# scale_AD7190.net
KiCad netlist of a schematic drawn in Altium Designer
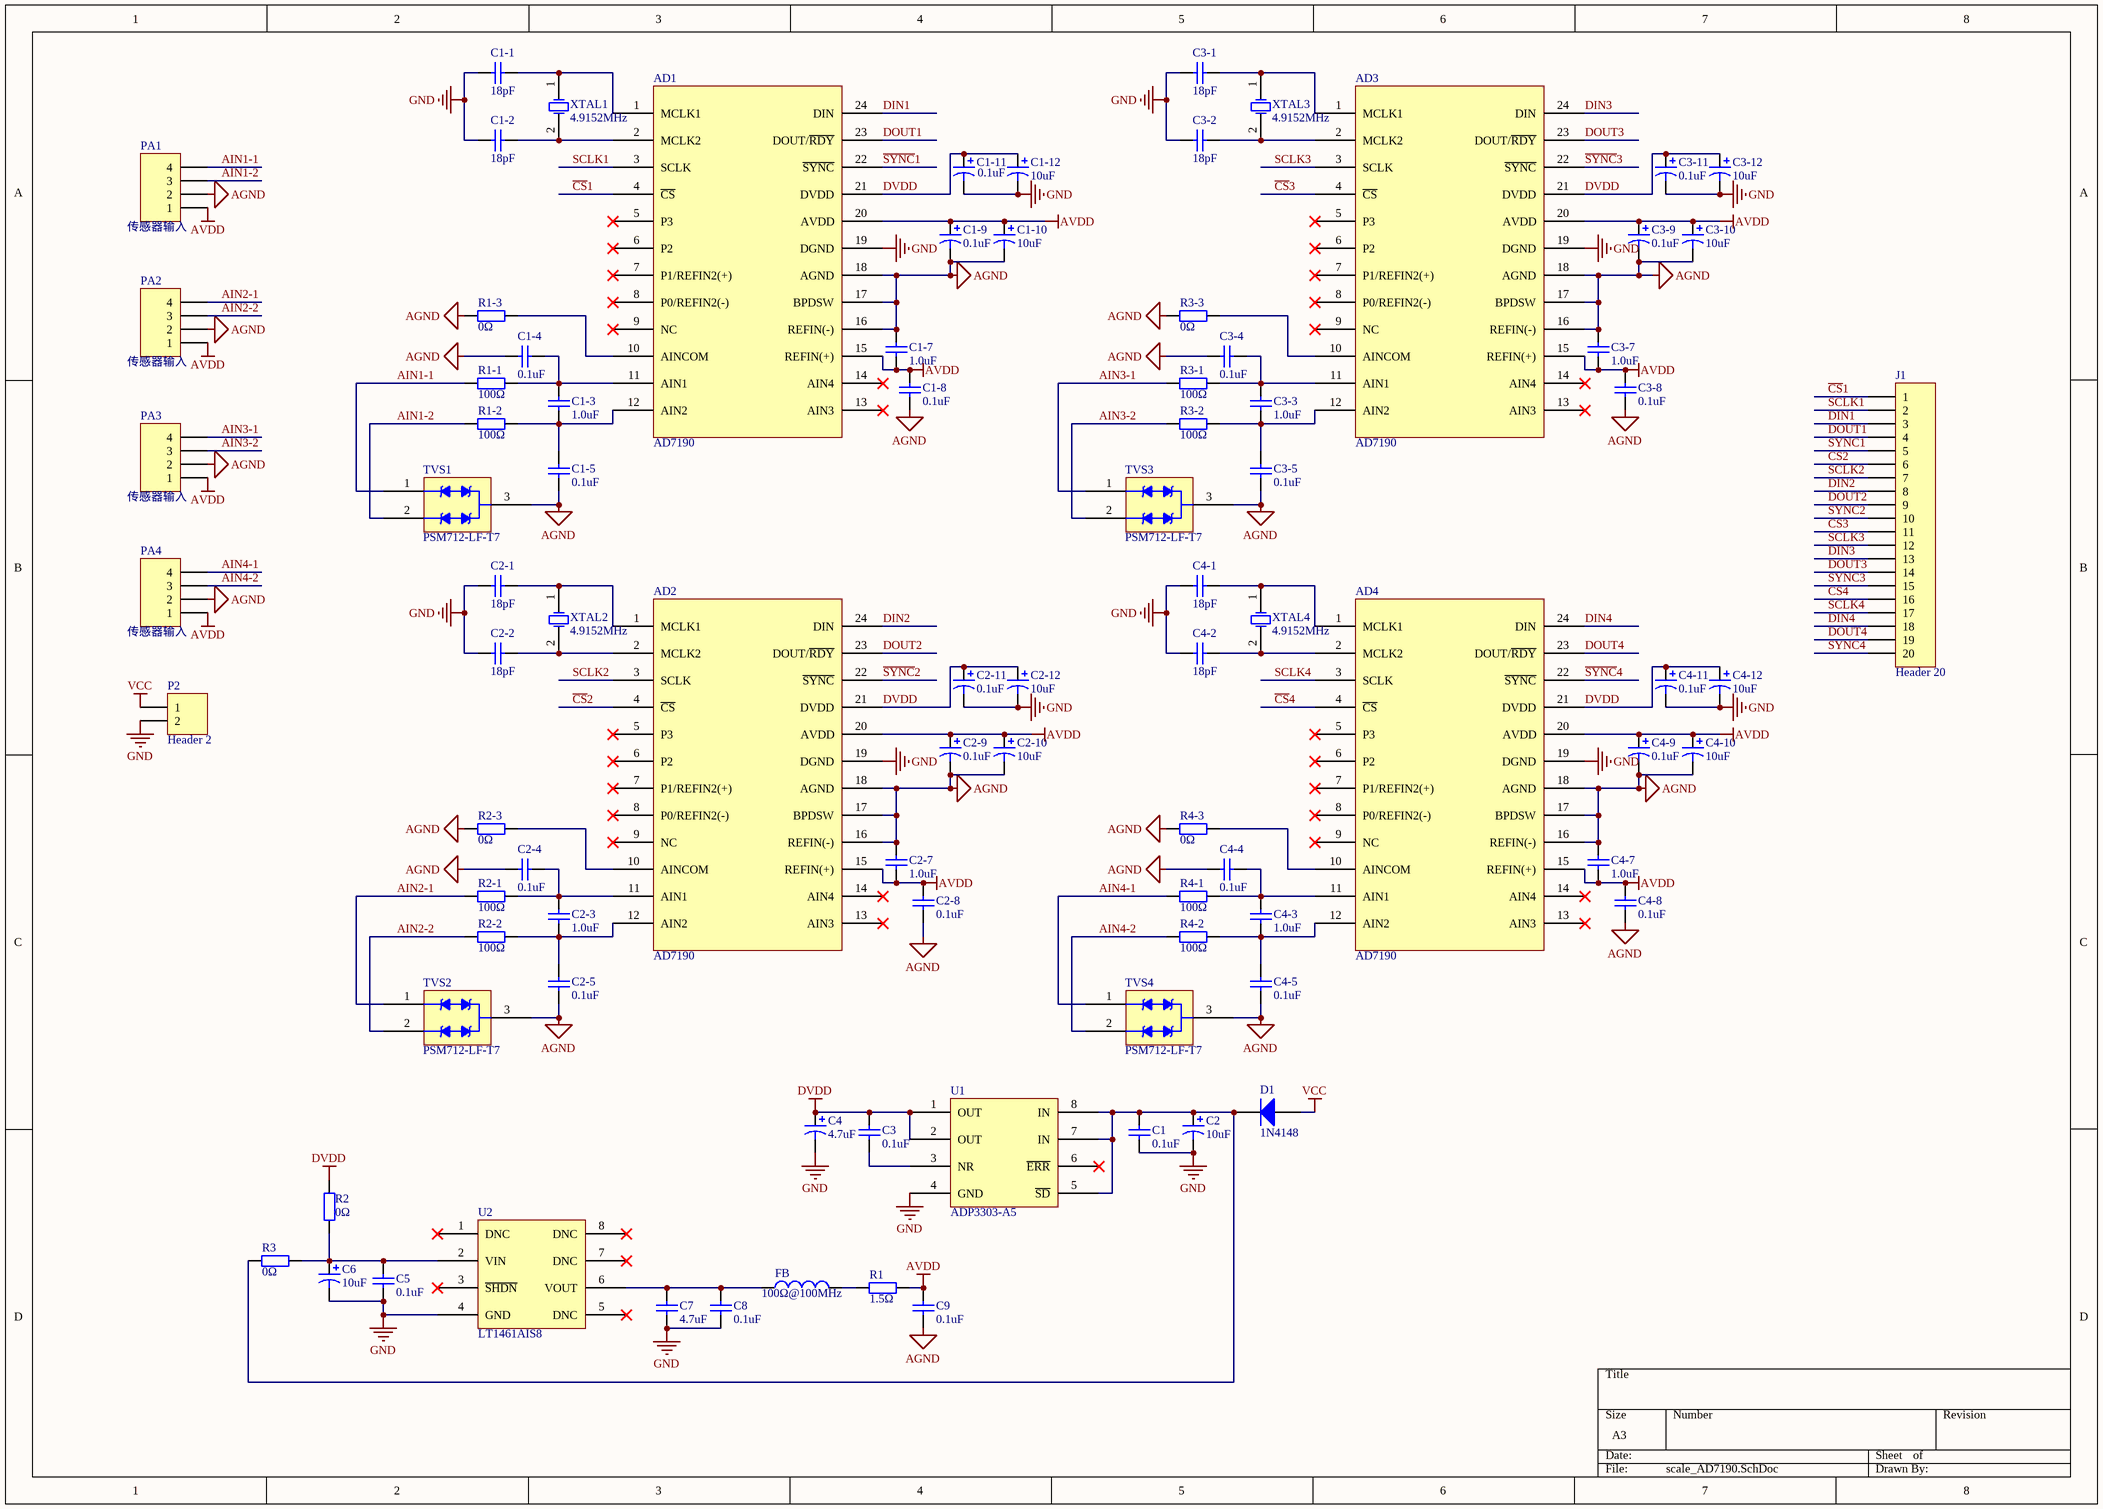
[diagram p0: scale_AD7190.SchDoc]

(export (version "E")
  (design (tool "Eeschema 10.0.6"))
  (components
    (comp (ref "AD1")
      (value "AD7190")
      (footprint "TSOP-24N_AD7190")
      (libsource (lib "scale_AD7190") (part "AD7190"))
    )
    (comp (ref "AD2")
      (value "AD7190")
      (footprint "TSOP-24N_AD7190")
      (libsource (lib "scale_AD7190") (part "AD7190"))
    )
    (comp (ref "AD3")
      (value "AD7190")
      (footprint "TSOP-24N_AD7190")
      (libsource (lib "scale_AD7190") (part "AD7190"))
    )
    (comp (ref "AD4")
      (value "AD7190")
      (footprint "TSOP-24N_AD7190")
      (libsource (lib "scale_AD7190") (part "AD7190"))
    )
    (comp (ref "C1")
      (value "0.1uF")
      (footprint "0805_C")
      (description "贴片电容")
      (libsource (lib "Miscellaneous Devices LC") (part "0402 1.0uF (105) 10% 25V"))
    )
    (comp (ref "C1-1")
      (value "18pF")
      (footprint "0805_C")
      (description "贴片电容")
      (libsource (lib "Miscellaneous Devices LC") (part "0402 15pF (150) 5% 50V"))
    )
    (comp (ref "C1-2")
      (value "18pF")
      (footprint "0805_C")
      (description "贴片电容")
      (libsource (lib "Miscellaneous Devices LC") (part "0402 15pF (150) 5% 50V"))
    )
    (comp (ref "C1-3")
      (value "1.0uF")
      (footprint "0805_C")
      (description "贴片电容")
      (libsource (lib "Miscellaneous Devices LC") (part "0402 1.0uF (105) 10% 25V"))
    )
    (comp (ref "C1-4")
      (value "0.1uF")
      (footprint "0805_C")
      (description "贴片电容")
      (libsource (lib "Miscellaneous Devices LC") (part "0402 1.0uF (105) 10% 25V"))
    )
    (comp (ref "C1-5")
      (value "0.1uF")
      (footprint "0805_C")
      (description "贴片电容")
      (libsource (lib "Miscellaneous Devices LC") (part "0402 1.0uF (105) 10% 25V"))
    )
    (comp (ref "C1-7")
      (value "1.0uF")
      (footprint "0805_C")
      (description "贴片电容")
      (libsource (lib "Miscellaneous Devices LC") (part "0402 1.0uF (105) 10% 25V"))
    )
    (comp (ref "C1-8")
      (value "0.1uF")
      (footprint "0805_C")
      (description "贴片电容")
      (libsource (lib "Miscellaneous Devices LC") (part "0402 1.0uF (105) 10% 25V"))
    )
    (comp (ref "C1-9")
      (value "0.1uF")
      (footprint "0805_C")
      (description "Polarized Capacitor (Surface Mount)")
      (fields (field (name "PUBLISHER") "Altium Limited"))
      (libsource (lib "Miscellaneous Devices") (part "Cap Pol3"))
    )
    (comp (ref "C1-10")
      (value "10uF")
      (footprint "0805_C")
      (description "Polarized Capacitor (Surface Mount)")
      (fields (field (name "PUBLISHER") "Altium Limited"))
      (libsource (lib "Miscellaneous Devices") (part "Cap Pol3"))
    )
    (comp (ref "C1-11")
      (value "0.1uF")
      (footprint "0805_C")
      (description "Polarized Capacitor (Surface Mount)")
      (fields (field (name "PUBLISHER") "Altium Limited"))
      (libsource (lib "Miscellaneous Devices") (part "Cap Pol3"))
    )
    (comp (ref "C1-12")
      (value "10uF")
      (footprint "0805_C")
      (description "Polarized Capacitor (Surface Mount)")
      (fields (field (name "PUBLISHER") "Altium Limited"))
      (libsource (lib "Miscellaneous Devices") (part "Cap Pol3"))
    )
    (comp (ref "C2")
      (value "10uF")
      (footprint "0805_C")
      (description "Polarized Capacitor (Surface Mount)")
      (fields (field (name "PUBLISHER") "Altium Limited"))
      (libsource (lib "Miscellaneous Devices") (part "Cap Pol3"))
    )
    (comp (ref "C2-1")
      (value "18pF")
      (footprint "0805_C")
      (description "贴片电容")
      (libsource (lib "Miscellaneous Devices LC") (part "0402 15pF (150) 5% 50V"))
    )
    (comp (ref "C2-2")
      (value "18pF")
      (footprint "0805_C")
      (description "贴片电容")
      (libsource (lib "Miscellaneous Devices LC") (part "0402 15pF (150) 5% 50V"))
    )
    (comp (ref "C2-3")
      (value "1.0uF")
      (footprint "0805_C")
      (description "贴片电容")
      (libsource (lib "Miscellaneous Devices LC") (part "0402 1.0uF (105) 10% 25V"))
    )
    (comp (ref "C2-4")
      (value "0.1uF")
      (footprint "0805_C")
      (description "贴片电容")
      (libsource (lib "Miscellaneous Devices LC") (part "0402 1.0uF (105) 10% 25V"))
    )
    (comp (ref "C2-5")
      (value "0.1uF")
      (footprint "0805_C")
      (description "贴片电容")
      (libsource (lib "Miscellaneous Devices LC") (part "0402 1.0uF (105) 10% 25V"))
    )
    (comp (ref "C2-7")
      (value "1.0uF")
      (footprint "0805_C")
      (description "贴片电容")
      (libsource (lib "Miscellaneous Devices LC") (part "0402 1.0uF (105) 10% 25V"))
    )
    (comp (ref "C2-8")
      (value "0.1uF")
      (footprint "0805_C")
      (description "贴片电容")
      (libsource (lib "Miscellaneous Devices LC") (part "0402 1.0uF (105) 10% 25V"))
    )
    (comp (ref "C2-9")
      (value "0.1uF")
      (footprint "0805_C")
      (description "Polarized Capacitor (Surface Mount)")
      (fields (field (name "PUBLISHER") "Altium Limited"))
      (libsource (lib "Miscellaneous Devices") (part "Cap Pol3"))
    )
    (comp (ref "C2-10")
      (value "10uF")
      (footprint "0805_C")
      (description "Polarized Capacitor (Surface Mount)")
      (fields (field (name "PUBLISHER") "Altium Limited"))
      (libsource (lib "Miscellaneous Devices") (part "Cap Pol3"))
    )
    (comp (ref "C2-11")
      (value "0.1uF")
      (footprint "0805_C")
      (description "Polarized Capacitor (Surface Mount)")
      (fields (field (name "PUBLISHER") "Altium Limited"))
      (libsource (lib "Miscellaneous Devices") (part "Cap Pol3"))
    )
    (comp (ref "C2-12")
      (value "10uF")
      (footprint "0805_C")
      (description "Polarized Capacitor (Surface Mount)")
      (fields (field (name "PUBLISHER") "Altium Limited"))
      (libsource (lib "Miscellaneous Devices") (part "Cap Pol3"))
    )
    (comp (ref "C3")
      (value "0.1uF")
      (footprint "0805_C")
      (description "贴片电容")
      (libsource (lib "Miscellaneous Devices LC") (part "0402 1.0uF (105) 10% 25V"))
    )
    (comp (ref "C3-1")
      (value "18pF")
      (footprint "0805_C")
      (description "贴片电容")
      (libsource (lib "Miscellaneous Devices LC") (part "0402 15pF (150) 5% 50V"))
    )
    (comp (ref "C3-2")
      (value "18pF")
      (footprint "0805_C")
      (description "贴片电容")
      (libsource (lib "Miscellaneous Devices LC") (part "0402 15pF (150) 5% 50V"))
    )
    (comp (ref "C3-3")
      (value "1.0uF")
      (footprint "0805_C")
      (description "贴片电容")
      (libsource (lib "Miscellaneous Devices LC") (part "0402 1.0uF (105) 10% 25V"))
    )
    (comp (ref "C3-4")
      (value "0.1uF")
      (footprint "0805_C")
      (description "贴片电容")
      (libsource (lib "Miscellaneous Devices LC") (part "0402 1.0uF (105) 10% 25V"))
    )
    (comp (ref "C3-5")
      (value "0.1uF")
      (footprint "0805_C")
      (description "贴片电容")
      (libsource (lib "Miscellaneous Devices LC") (part "0402 1.0uF (105) 10% 25V"))
    )
    (comp (ref "C3-7")
      (value "1.0uF")
      (footprint "0805_C")
      (description "贴片电容")
      (libsource (lib "Miscellaneous Devices LC") (part "0402 1.0uF (105) 10% 25V"))
    )
    (comp (ref "C3-8")
      (value "0.1uF")
      (footprint "0805_C")
      (description "贴片电容")
      (libsource (lib "Miscellaneous Devices LC") (part "0402 1.0uF (105) 10% 25V"))
    )
    (comp (ref "C3-9")
      (value "0.1uF")
      (footprint "0805_C")
      (description "Polarized Capacitor (Surface Mount)")
      (fields (field (name "PUBLISHER") "Altium Limited"))
      (libsource (lib "Miscellaneous Devices") (part "Cap Pol3"))
    )
    (comp (ref "C3-10")
      (value "10uF")
      (footprint "0805_C")
      (description "Polarized Capacitor (Surface Mount)")
      (fields (field (name "PUBLISHER") "Altium Limited"))
      (libsource (lib "Miscellaneous Devices") (part "Cap Pol3"))
    )
    (comp (ref "C3-11")
      (value "0.1uF")
      (footprint "0805_C")
      (description "Polarized Capacitor (Surface Mount)")
      (fields (field (name "PUBLISHER") "Altium Limited"))
      (libsource (lib "Miscellaneous Devices") (part "Cap Pol3"))
    )
    (comp (ref "C3-12")
      (value "10uF")
      (footprint "0805_C")
      (description "Polarized Capacitor (Surface Mount)")
      (fields (field (name "PUBLISHER") "Altium Limited"))
      (libsource (lib "Miscellaneous Devices") (part "Cap Pol3"))
    )
    (comp (ref "C4")
      (value "4.7uF")
      (footprint "0805_C")
      (description "Polarized Capacitor (Surface Mount)")
      (fields (field (name "PUBLISHER") "Altium Limited"))
      (libsource (lib "Miscellaneous Devices") (part "Cap Pol3"))
    )
    (comp (ref "C4-1")
      (value "18pF")
      (footprint "0805_C")
      (description "贴片电容")
      (libsource (lib "Miscellaneous Devices LC") (part "0402 15pF (150) 5% 50V"))
    )
    (comp (ref "C4-2")
      (value "18pF")
      (footprint "0805_C")
      (description "贴片电容")
      (libsource (lib "Miscellaneous Devices LC") (part "0402 15pF (150) 5% 50V"))
    )
    (comp (ref "C4-3")
      (value "1.0uF")
      (footprint "0805_C")
      (description "贴片电容")
      (libsource (lib "Miscellaneous Devices LC") (part "0402 1.0uF (105) 10% 25V"))
    )
    (comp (ref "C4-4")
      (value "0.1uF")
      (footprint "0805_C")
      (description "贴片电容")
      (libsource (lib "Miscellaneous Devices LC") (part "0402 1.0uF (105) 10% 25V"))
    )
    (comp (ref "C4-5")
      (value "0.1uF")
      (footprint "0805_C")
      (description "贴片电容")
      (libsource (lib "Miscellaneous Devices LC") (part "0402 1.0uF (105) 10% 25V"))
    )
    (comp (ref "C4-7")
      (value "1.0uF")
      (footprint "0805_C")
      (description "贴片电容")
      (libsource (lib "Miscellaneous Devices LC") (part "0402 1.0uF (105) 10% 25V"))
    )
    (comp (ref "C4-8")
      (value "0.1uF")
      (footprint "0805_C")
      (description "贴片电容")
      (libsource (lib "Miscellaneous Devices LC") (part "0402 1.0uF (105) 10% 25V"))
    )
    (comp (ref "C4-9")
      (value "0.1uF")
      (footprint "0805_C")
      (description "Polarized Capacitor (Surface Mount)")
      (fields (field (name "PUBLISHER") "Altium Limited"))
      (libsource (lib "Miscellaneous Devices") (part "Cap Pol3"))
    )
    (comp (ref "C4-10")
      (value "10uF")
      (footprint "0805_C")
      (description "Polarized Capacitor (Surface Mount)")
      (fields (field (name "PUBLISHER") "Altium Limited"))
      (libsource (lib "Miscellaneous Devices") (part "Cap Pol3"))
    )
    (comp (ref "C4-11")
      (value "0.1uF")
      (footprint "0805_C")
      (description "Polarized Capacitor (Surface Mount)")
      (fields (field (name "PUBLISHER") "Altium Limited"))
      (libsource (lib "Miscellaneous Devices") (part "Cap Pol3"))
    )
    (comp (ref "C4-12")
      (value "10uF")
      (footprint "0805_C")
      (description "Polarized Capacitor (Surface Mount)")
      (fields (field (name "PUBLISHER") "Altium Limited"))
      (libsource (lib "Miscellaneous Devices") (part "Cap Pol3"))
    )
    (comp (ref "C5")
      (value "0.1uF")
      (footprint "0805_C")
      (description "贴片电容")
      (libsource (lib "Miscellaneous Devices LC") (part "0402 1.0uF (105) 10% 25V"))
    )
    (comp (ref "C6")
      (value "10uF")
      (footprint "0805_C")
      (description "Polarized Capacitor (Surface Mount)")
      (fields (field (name "PUBLISHER") "Altium Limited"))
      (libsource (lib "Miscellaneous Devices") (part "Cap Pol3"))
    )
    (comp (ref "C7")
      (value "4.7uF")
      (footprint "0805_C")
      (description "贴片电容")
      (libsource (lib "Miscellaneous Devices LC") (part "0402 1.0uF (105) 10% 25V"))
    )
    (comp (ref "C8")
      (value "0.1uF")
      (footprint "0805_C")
      (description "贴片电容")
      (libsource (lib "Miscellaneous Devices LC") (part "0402 1.0uF (105) 10% 25V"))
    )
    (comp (ref "C9")
      (value "0.1uF")
      (footprint "0805_C")
      (description "贴片电容")
      (libsource (lib "Miscellaneous Devices LC") (part "0402 1.0uF (105) 10% 25V"))
    )
    (comp (ref "D1")
      (value "1N4148")
      (footprint "SOD-323")
      (description "High Conductance Fast Diode")
      (fields (field (name "PUBLISHER") "Altium Limited"))
      (libsource (lib "Miscellaneous Devices") (part "Diode 1N4148"))
    )
    (comp (ref "FB")
      (value "100Ω@100MHz")
      (footprint "0805_L")
      (description "Inductor")
      (fields (field (name "PUBLISHER") "Altium Limited"))
      (libsource (lib "Miscellaneous Devices") (part "Inductor"))
    )
    (comp (ref "J1")
      (value "Header 20")
      (footprint "HDR1X20")
      (description "Header, 20-Pin")
      (fields (field (name "PUBLISHER") "Altium Limited"))
      (libsource (lib "Miscellaneous Connectors") (part "Header 20"))
    )
    (comp (ref "P2")
      (value "Header 2")
      (footprint "端子2×5.08")
      (description "Header, 2-Pin")
      (fields (field (name "PUBLISHER") "Altium Limited"))
      (libsource (lib "Miscellaneous Connectors") (part "Header 2"))
    )
    (comp (ref "PA1")
      (value "传感器输入")
      (footprint "端子4*5.08")
      (description "Header, 4-Pin")
      (fields (field (name "PUBLISHER") "Altium Limited"))
      (libsource (lib "Miscellaneous Connectors") (part "Header 4"))
    )
    (comp (ref "PA2")
      (value "传感器输入")
      (footprint "端子4*5.08")
      (description "Header, 4-Pin")
      (fields (field (name "PUBLISHER") "Altium Limited"))
      (libsource (lib "Miscellaneous Connectors") (part "Header 4"))
    )
    (comp (ref "PA3")
      (value "传感器输入")
      (footprint "端子4*5.08")
      (description "Header, 4-Pin")
      (fields (field (name "PUBLISHER") "Altium Limited"))
      (libsource (lib "Miscellaneous Connectors") (part "Header 4"))
    )
    (comp (ref "PA4")
      (value "传感器输入")
      (footprint "端子4*5.08")
      (description "Header, 4-Pin")
      (fields (field (name "PUBLISHER") "Altium Limited"))
      (libsource (lib "Miscellaneous Connectors") (part "Header 4"))
    )
    (comp (ref "R1")
      (value "1.5Ω")
      (footprint "0805_R")
      (description "贴片电阻")
      (libsource (lib "Miscellaneous Devices LC") (part "0402 1.2KΩ (1201) 1%"))
    )
    (comp (ref "R1-1")
      (value "100Ω")
      (footprint "0805_R")
      (description "贴片电阻")
      (libsource (lib "Miscellaneous Devices LC") (part "0402 100Ω (1000) 1%"))
    )
    (comp (ref "R1-2")
      (value "100Ω")
      (footprint "0805_R")
      (description "贴片电阻")
      (libsource (lib "Miscellaneous Devices LC") (part "0402 100Ω (1000) 1%"))
    )
    (comp (ref "R1-3")
      (value "0Ω")
      (footprint "0805_R")
      (description "贴片电阻")
      (libsource (lib "Miscellaneous Devices LC") (part "0402 100Ω (1000) 1%"))
    )
    (comp (ref "R2")
      (value "0Ω")
      (footprint "0805_R")
      (description "贴片电阻")
      (libsource (lib "") (part "0402 100Ω (1000) 1%_1"))
    )
    (comp (ref "R2-1")
      (value "100Ω")
      (footprint "0805_R")
      (description "贴片电阻")
      (libsource (lib "Miscellaneous Devices LC") (part "0402 100Ω (1000) 1%"))
    )
    (comp (ref "R2-2")
      (value "100Ω")
      (footprint "0805_R")
      (description "贴片电阻")
      (libsource (lib "Miscellaneous Devices LC") (part "0402 100Ω (1000) 1%"))
    )
    (comp (ref "R2-3")
      (value "0Ω")
      (footprint "0805_R")
      (description "贴片电阻")
      (libsource (lib "Miscellaneous Devices LC") (part "0402 100Ω (1000) 1%"))
    )
    (comp (ref "R3")
      (value "0Ω")
      (footprint "0805_R")
      (description "贴片电阻")
      (libsource (lib "Miscellaneous Devices LC") (part "0402 100Ω (1000) 1%"))
    )
    (comp (ref "R3-1")
      (value "100Ω")
      (footprint "0805_R")
      (description "贴片电阻")
      (libsource (lib "Miscellaneous Devices LC") (part "0402 100Ω (1000) 1%"))
    )
    (comp (ref "R3-2")
      (value "100Ω")
      (footprint "0805_R")
      (description "贴片电阻")
      (libsource (lib "Miscellaneous Devices LC") (part "0402 100Ω (1000) 1%"))
    )
    (comp (ref "R3-3")
      (value "0Ω")
      (footprint "0805_R")
      (description "贴片电阻")
      (libsource (lib "Miscellaneous Devices LC") (part "0402 100Ω (1000) 1%"))
    )
    (comp (ref "R4-1")
      (value "100Ω")
      (footprint "0805_R")
      (description "贴片电阻")
      (libsource (lib "Miscellaneous Devices LC") (part "0402 100Ω (1000) 1%"))
    )
    (comp (ref "R4-2")
      (value "100Ω")
      (footprint "0805_R")
      (description "贴片电阻")
      (libsource (lib "Miscellaneous Devices LC") (part "0402 100Ω (1000) 1%"))
    )
    (comp (ref "R4-3")
      (value "0Ω")
      (footprint "0805_R")
      (description "贴片电阻")
      (libsource (lib "Miscellaneous Devices LC") (part "0402 100Ω (1000) 1%"))
    )
    (comp (ref "TVS1")
      (value "PSM712-LF-T7")
      (footprint "SOT-23(SOT-23-3)")
      (description "TVS")
      (libsource (lib "Miscellaneous Devices LC") (part "PSM712-LF-T7_[C32677]"))
    )
    (comp (ref "TVS2")
      (value "PSM712-LF-T7")
      (footprint "SOT-23(SOT-23-3)")
      (description "TVS")
      (libsource (lib "Miscellaneous Devices LC") (part "PSM712-LF-T7_[C32677]"))
    )
    (comp (ref "TVS3")
      (value "PSM712-LF-T7")
      (footprint "SOT-23(SOT-23-3)")
      (description "TVS")
      (libsource (lib "Miscellaneous Devices LC") (part "PSM712-LF-T7_[C32677]"))
    )
    (comp (ref "TVS4")
      (value "PSM712-LF-T7")
      (footprint "SOT-23(SOT-23-3)")
      (description "TVS")
      (libsource (lib "Miscellaneous Devices LC") (part "PSM712-LF-T7_[C32677]"))
    )
    (comp (ref "U1")
      (value "ADP3303-A5")
      (footprint "SOIC-8N-ADP3303-A5")
      (libsource (lib "scale_AD7190") (part "ADP3303"))
    )
    (comp (ref "U2")
      (value "LT1461AIS8")
      (footprint "SOIC-8N-LT1416")
      (libsource (lib "scale_AD7190") (part "LT1461AIS8"))
    )
    (comp (ref "XTAL1")
      (value "4.9152MHz")
      (footprint "SMD-3225_4P")
      (description "Crystal Oscillator")
      (fields (field (name "PUBLISHER") "Altium Limited"))
      (libsource (lib "Miscellaneous Devices") (part "XTAL"))
    )
    (comp (ref "XTAL2")
      (value "4.9152MHz")
      (footprint "SMD-3225_4P")
      (description "Crystal Oscillator")
      (fields (field (name "PUBLISHER") "Altium Limited"))
      (libsource (lib "Miscellaneous Devices") (part "XTAL"))
    )
    (comp (ref "XTAL3")
      (value "4.9152MHz")
      (footprint "SMD-3225_4P")
      (description "Crystal Oscillator")
      (fields (field (name "PUBLISHER") "Altium Limited"))
      (libsource (lib "Miscellaneous Devices") (part "XTAL"))
    )
    (comp (ref "XTAL4")
      (value "4.9152MHz")
      (footprint "SMD-3225_4P")
      (description "Crystal Oscillator")
      (fields (field (name "PUBLISHER") "Altium Limited"))
      (libsource (lib "Miscellaneous Devices") (part "XTAL"))
    )
  )
  (nets
    (net (code "1") (name "/AIN1-1") (class "Default")
      (node (ref "PA1") (pin "4") (pinfunction "4_4") (pintype "passive"))
      (node (ref "R1-1") (pin "1") (pinfunction "1_1") (pintype "passive"))
      (node (ref "TVS1") (pin "1") (pinfunction "1_1") (pintype "passive"))
    )
    (net (code "2") (name "/AIN1-2") (class "Default")
      (node (ref "PA1") (pin "3") (pinfunction "3_3") (pintype "passive"))
      (node (ref "R1-2") (pin "1") (pinfunction "1_1") (pintype "passive"))
      (node (ref "TVS1") (pin "2") (pinfunction "2_2") (pintype "passive"))
    )
    (net (code "3") (name "/AIN2-1") (class "Default")
      (node (ref "PA2") (pin "4") (pinfunction "4_4") (pintype "passive"))
      (node (ref "R2-1") (pin "1") (pinfunction "1_1") (pintype "passive"))
      (node (ref "TVS2") (pin "1") (pinfunction "1_1") (pintype "passive"))
    )
    (net (code "4") (name "/AIN2-2") (class "Default")
      (node (ref "PA2") (pin "3") (pinfunction "3_3") (pintype "passive"))
      (node (ref "R2-2") (pin "1") (pinfunction "1_1") (pintype "passive"))
      (node (ref "TVS2") (pin "2") (pinfunction "2_2") (pintype "passive"))
    )
    (net (code "5") (name "/AIN3-1") (class "Default")
      (node (ref "PA3") (pin "4") (pinfunction "4_4") (pintype "passive"))
      (node (ref "R3-1") (pin "1") (pinfunction "1_1") (pintype "passive"))
      (node (ref "TVS3") (pin "1") (pinfunction "1_1") (pintype "passive"))
    )
    (net (code "6") (name "/AIN3-2") (class "Default")
      (node (ref "PA3") (pin "3") (pinfunction "3_3") (pintype "passive"))
      (node (ref "R3-2") (pin "1") (pinfunction "1_1") (pintype "passive"))
      (node (ref "TVS3") (pin "2") (pinfunction "2_2") (pintype "passive"))
    )
    (net (code "7") (name "/AIN4-1") (class "Default")
      (node (ref "PA4") (pin "4") (pinfunction "4_4") (pintype "passive"))
      (node (ref "R4-1") (pin "1") (pinfunction "1_1") (pintype "passive"))
      (node (ref "TVS4") (pin "1") (pinfunction "1_1") (pintype "passive"))
    )
    (net (code "8") (name "/AIN4-2") (class "Default")
      (node (ref "PA4") (pin "3") (pinfunction "3_3") (pintype "passive"))
      (node (ref "R4-2") (pin "1") (pinfunction "1_1") (pintype "passive"))
      (node (ref "TVS4") (pin "2") (pinfunction "2_2") (pintype "passive"))
    )
    (net (code "9") (name "/DIN1") (class "Default")
      (node (ref "AD1") (pin "24") (pinfunction "DIN_24") (pintype "passive"))
      (node (ref "J1") (pin "3") (pinfunction "3_3") (pintype "passive"))
    )
    (net (code "10") (name "/DIN2") (class "Default")
      (node (ref "AD2") (pin "24") (pinfunction "DIN_24") (pintype "passive"))
      (node (ref "J1") (pin "8") (pinfunction "8_8") (pintype "passive"))
    )
    (net (code "11") (name "/DIN3") (class "Default")
      (node (ref "AD3") (pin "24") (pinfunction "DIN_24") (pintype "passive"))
      (node (ref "J1") (pin "13") (pinfunction "13_13") (pintype "passive"))
    )
    (net (code "12") (name "/DIN4") (class "Default")
      (node (ref "AD4") (pin "24") (pinfunction "DIN_24") (pintype "passive"))
      (node (ref "J1") (pin "18") (pinfunction "18_18") (pintype "passive"))
    )
    (net (code "13") (name "/DOUT1") (class "Default")
      (node (ref "AD1") (pin "23") (pinfunction "DOUT/~{RDY}_23") (pintype "passive"))
      (node (ref "J1") (pin "4") (pinfunction "4_4") (pintype "passive"))
    )
    (net (code "14") (name "/DOUT2") (class "Default")
      (node (ref "AD2") (pin "23") (pinfunction "DOUT/~{RDY}_23") (pintype "passive"))
      (node (ref "J1") (pin "9") (pinfunction "9_9") (pintype "passive"))
    )
    (net (code "15") (name "/DOUT3") (class "Default")
      (node (ref "AD3") (pin "23") (pinfunction "DOUT/~{RDY}_23") (pintype "passive"))
      (node (ref "J1") (pin "14") (pinfunction "14_14") (pintype "passive"))
    )
    (net (code "16") (name "/DOUT4") (class "Default")
      (node (ref "AD4") (pin "23") (pinfunction "DOUT/~{RDY}_23") (pintype "passive"))
      (node (ref "J1") (pin "19") (pinfunction "19_19") (pintype "passive"))
    )
    (net (code "17") (name "/SCLK1") (class "Default")
      (node (ref "AD1") (pin "3") (pinfunction "SCLK_3") (pintype "passive"))
      (node (ref "J1") (pin "2") (pinfunction "2_2") (pintype "passive"))
    )
    (net (code "18") (name "/SCLK2") (class "Default")
      (node (ref "AD2") (pin "3") (pinfunction "SCLK_3") (pintype "passive"))
      (node (ref "J1") (pin "7") (pinfunction "7_7") (pintype "passive"))
    )
    (net (code "19") (name "/SCLK3") (class "Default")
      (node (ref "AD3") (pin "3") (pinfunction "SCLK_3") (pintype "passive"))
      (node (ref "J1") (pin "12") (pinfunction "12_12") (pintype "passive"))
    )
    (net (code "20") (name "/SCLK4") (class "Default")
      (node (ref "AD4") (pin "3") (pinfunction "SCLK_3") (pintype "passive"))
      (node (ref "J1") (pin "17") (pinfunction "17_17") (pintype "passive"))
    )
    (net (code "21") (name "/~{CS}1") (class "Default")
      (node (ref "AD1") (pin "4") (pinfunction "~{CS}_4") (pintype "passive"))
      (node (ref "J1") (pin "1") (pinfunction "1_1") (pintype "passive"))
    )
    (net (code "22") (name "/~{CS}2") (class "Default")
      (node (ref "AD2") (pin "4") (pinfunction "~{CS}_4") (pintype "passive"))
      (node (ref "J1") (pin "6") (pinfunction "6_6") (pintype "passive"))
    )
    (net (code "23") (name "/~{CS}3") (class "Default")
      (node (ref "AD3") (pin "4") (pinfunction "~{CS}_4") (pintype "passive"))
      (node (ref "J1") (pin "11") (pinfunction "11_11") (pintype "passive"))
    )
    (net (code "24") (name "/~{CS}4") (class "Default")
      (node (ref "AD4") (pin "4") (pinfunction "~{CS}_4") (pintype "passive"))
      (node (ref "J1") (pin "16") (pinfunction "16_16") (pintype "passive"))
    )
    (net (code "25") (name "/~{SYNC}1") (class "Default")
      (node (ref "AD1") (pin "22") (pinfunction "~{SYNC}_22") (pintype "passive"))
      (node (ref "J1") (pin "5") (pinfunction "5_5") (pintype "passive"))
    )
    (net (code "26") (name "/~{SYNC}2") (class "Default")
      (node (ref "AD2") (pin "22") (pinfunction "~{SYNC}_22") (pintype "passive"))
      (node (ref "J1") (pin "10") (pinfunction "10_10") (pintype "passive"))
    )
    (net (code "27") (name "/~{SYNC}3") (class "Default")
      (node (ref "AD3") (pin "22") (pinfunction "~{SYNC}_22") (pintype "passive"))
      (node (ref "J1") (pin "15") (pinfunction "15_15") (pintype "passive"))
    )
    (net (code "28") (name "/~{SYNC}4") (class "Default")
      (node (ref "AD4") (pin "22") (pinfunction "~{SYNC}_22") (pintype "passive"))
      (node (ref "J1") (pin "20") (pinfunction "20_20") (pintype "passive"))
    )
    (net (code "29") (name "AGND") (class "Default")
      (node (ref "AD1") (pin "16") (pinfunction "REFIN(-)_16") (pintype "passive"))
      (node (ref "AD1") (pin "17") (pinfunction "BPDSW_17") (pintype "passive"))
      (node (ref "AD1") (pin "18") (pinfunction "AGND_18") (pintype "passive"))
      (node (ref "AD2") (pin "16") (pinfunction "REFIN(-)_16") (pintype "passive"))
      (node (ref "AD2") (pin "17") (pinfunction "BPDSW_17") (pintype "passive"))
      (node (ref "AD2") (pin "18") (pinfunction "AGND_18") (pintype "passive"))
      (node (ref "AD3") (pin "16") (pinfunction "REFIN(-)_16") (pintype "passive"))
      (node (ref "AD3") (pin "17") (pinfunction "BPDSW_17") (pintype "passive"))
      (node (ref "AD3") (pin "18") (pinfunction "AGND_18") (pintype "passive"))
      (node (ref "AD4") (pin "16") (pinfunction "REFIN(-)_16") (pintype "passive"))
      (node (ref "AD4") (pin "17") (pinfunction "BPDSW_17") (pintype "passive"))
      (node (ref "AD4") (pin "18") (pinfunction "AGND_18") (pintype "passive"))
      (node (ref "C1-10") (pin "2") (pinfunction "2_2") (pintype "passive"))
      (node (ref "C1-4") (pin "2") (pinfunction "2_2") (pintype "passive"))
      (node (ref "C1-5") (pin "2") (pinfunction "2_2") (pintype "passive"))
      (node (ref "C1-7") (pin "1") (pinfunction "1_1") (pintype "passive"))
      (node (ref "C1-8") (pin "1") (pinfunction "1_1") (pintype "passive"))
      (node (ref "C1-9") (pin "2") (pinfunction "2_2") (pintype "passive"))
      (node (ref "C2-10") (pin "2") (pinfunction "2_2") (pintype "passive"))
      (node (ref "C2-4") (pin "2") (pinfunction "2_2") (pintype "passive"))
      (node (ref "C2-5") (pin "2") (pinfunction "2_2") (pintype "passive"))
      (node (ref "C2-7") (pin "1") (pinfunction "1_1") (pintype "passive"))
      (node (ref "C2-8") (pin "1") (pinfunction "1_1") (pintype "passive"))
      (node (ref "C2-9") (pin "2") (pinfunction "2_2") (pintype "passive"))
      (node (ref "C3-10") (pin "2") (pinfunction "2_2") (pintype "passive"))
      (node (ref "C3-4") (pin "2") (pinfunction "2_2") (pintype "passive"))
      (node (ref "C3-5") (pin "2") (pinfunction "2_2") (pintype "passive"))
      (node (ref "C3-7") (pin "1") (pinfunction "1_1") (pintype "passive"))
      (node (ref "C3-8") (pin "1") (pinfunction "1_1") (pintype "passive"))
      (node (ref "C3-9") (pin "2") (pinfunction "2_2") (pintype "passive"))
      (node (ref "C4-10") (pin "2") (pinfunction "2_2") (pintype "passive"))
      (node (ref "C4-4") (pin "2") (pinfunction "2_2") (pintype "passive"))
      (node (ref "C4-5") (pin "2") (pinfunction "2_2") (pintype "passive"))
      (node (ref "C4-7") (pin "1") (pinfunction "1_1") (pintype "passive"))
      (node (ref "C4-8") (pin "1") (pinfunction "1_1") (pintype "passive"))
      (node (ref "C4-9") (pin "2") (pinfunction "2_2") (pintype "passive"))
      (node (ref "C9") (pin "2") (pinfunction "2_2") (pintype "passive"))
      (node (ref "PA1") (pin "2") (pinfunction "2_2") (pintype "passive"))
      (node (ref "PA2") (pin "2") (pinfunction "2_2") (pintype "passive"))
      (node (ref "PA3") (pin "2") (pinfunction "2_2") (pintype "passive"))
      (node (ref "PA4") (pin "2") (pinfunction "2_2") (pintype "passive"))
      (node (ref "R1-3") (pin "1") (pinfunction "1_1") (pintype "passive"))
      (node (ref "R2-3") (pin "1") (pinfunction "1_1") (pintype "passive"))
      (node (ref "R3-3") (pin "1") (pinfunction "1_1") (pintype "passive"))
      (node (ref "R4-3") (pin "1") (pinfunction "1_1") (pintype "passive"))
      (node (ref "TVS1") (pin "3") (pinfunction "3_3") (pintype "passive"))
      (node (ref "TVS2") (pin "3") (pinfunction "3_3") (pintype "passive"))
      (node (ref "TVS3") (pin "3") (pinfunction "3_3") (pintype "passive"))
      (node (ref "TVS4") (pin "3") (pinfunction "3_3") (pintype "passive"))
    )
    (net (code "30") (name "AVDD") (class "Default")
      (node (ref "AD1") (pin "15") (pinfunction "REFIN(+)_15") (pintype "passive"))
      (node (ref "AD1") (pin "20") (pinfunction "AVDD_20") (pintype "passive"))
      (node (ref "AD2") (pin "15") (pinfunction "REFIN(+)_15") (pintype "passive"))
      (node (ref "AD2") (pin "20") (pinfunction "AVDD_20") (pintype "passive"))
      (node (ref "AD3") (pin "15") (pinfunction "REFIN(+)_15") (pintype "passive"))
      (node (ref "AD3") (pin "20") (pinfunction "AVDD_20") (pintype "passive"))
      (node (ref "AD4") (pin "15") (pinfunction "REFIN(+)_15") (pintype "passive"))
      (node (ref "AD4") (pin "20") (pinfunction "AVDD_20") (pintype "passive"))
      (node (ref "C1-10") (pin "1") (pinfunction "1_1") (pintype "passive"))
      (node (ref "C1-7") (pin "2") (pinfunction "2_2") (pintype "passive"))
      (node (ref "C1-8") (pin "2") (pinfunction "2_2") (pintype "passive"))
      (node (ref "C1-9") (pin "1") (pinfunction "1_1") (pintype "passive"))
      (node (ref "C2-10") (pin "1") (pinfunction "1_1") (pintype "passive"))
      (node (ref "C2-7") (pin "2") (pinfunction "2_2") (pintype "passive"))
      (node (ref "C2-8") (pin "2") (pinfunction "2_2") (pintype "passive"))
      (node (ref "C2-9") (pin "1") (pinfunction "1_1") (pintype "passive"))
      (node (ref "C3-10") (pin "1") (pinfunction "1_1") (pintype "passive"))
      (node (ref "C3-7") (pin "2") (pinfunction "2_2") (pintype "passive"))
      (node (ref "C3-8") (pin "2") (pinfunction "2_2") (pintype "passive"))
      (node (ref "C3-9") (pin "1") (pinfunction "1_1") (pintype "passive"))
      (node (ref "C4-10") (pin "1") (pinfunction "1_1") (pintype "passive"))
      (node (ref "C4-7") (pin "2") (pinfunction "2_2") (pintype "passive"))
      (node (ref "C4-8") (pin "2") (pinfunction "2_2") (pintype "passive"))
      (node (ref "C4-9") (pin "1") (pinfunction "1_1") (pintype "passive"))
      (node (ref "C9") (pin "1") (pinfunction "1_1") (pintype "passive"))
      (node (ref "PA1") (pin "1") (pinfunction "1_1") (pintype "passive"))
      (node (ref "PA2") (pin "1") (pinfunction "1_1") (pintype "passive"))
      (node (ref "PA3") (pin "1") (pinfunction "1_1") (pintype "passive"))
      (node (ref "PA4") (pin "1") (pinfunction "1_1") (pintype "passive"))
      (node (ref "R1") (pin "2") (pinfunction "2_2") (pintype "passive"))
    )
    (net (code "31") (name "DVDD") (class "Default")
      (node (ref "AD1") (pin "21") (pinfunction "DVDD_21") (pintype "passive"))
      (node (ref "AD2") (pin "21") (pinfunction "DVDD_21") (pintype "passive"))
      (node (ref "AD3") (pin "21") (pinfunction "DVDD_21") (pintype "passive"))
      (node (ref "AD4") (pin "21") (pinfunction "DVDD_21") (pintype "passive"))
      (node (ref "C1-11") (pin "1") (pinfunction "1_1") (pintype "passive"))
      (node (ref "C1-12") (pin "1") (pinfunction "1_1") (pintype "passive"))
      (node (ref "C2-11") (pin "1") (pinfunction "1_1") (pintype "passive"))
      (node (ref "C2-12") (pin "1") (pinfunction "1_1") (pintype "passive"))
      (node (ref "C3") (pin "1") (pinfunction "1_1") (pintype "passive"))
      (node (ref "C3-11") (pin "1") (pinfunction "1_1") (pintype "passive"))
      (node (ref "C3-12") (pin "1") (pinfunction "1_1") (pintype "passive"))
      (node (ref "C4") (pin "1") (pinfunction "1_1") (pintype "passive"))
      (node (ref "C4-11") (pin "1") (pinfunction "1_1") (pintype "passive"))
      (node (ref "C4-12") (pin "1") (pinfunction "1_1") (pintype "passive"))
      (node (ref "R2") (pin "2") (pinfunction "2_2") (pintype "passive"))
      (node (ref "U1") (pin "1") (pinfunction "OUT_1") (pintype "passive"))
      (node (ref "U1") (pin "2") (pinfunction "OUT_2") (pintype "passive"))
    )
    (net (code "32") (name "GND") (class "Default")
      (node (ref "AD1") (pin "19") (pinfunction "DGND_19") (pintype "passive"))
      (node (ref "AD2") (pin "19") (pinfunction "DGND_19") (pintype "passive"))
      (node (ref "AD3") (pin "19") (pinfunction "DGND_19") (pintype "passive"))
      (node (ref "AD4") (pin "19") (pinfunction "DGND_19") (pintype "passive"))
      (node (ref "C1") (pin "2") (pinfunction "2_2") (pintype "passive"))
      (node (ref "C1-1") (pin "1") (pinfunction "1_1") (pintype "passive"))
      (node (ref "C1-11") (pin "2") (pinfunction "2_2") (pintype "passive"))
      (node (ref "C1-12") (pin "2") (pinfunction "2_2") (pintype "passive"))
      (node (ref "C1-2") (pin "1") (pinfunction "1_1") (pintype "passive"))
      (node (ref "C2") (pin "2") (pinfunction "2_2") (pintype "passive"))
      (node (ref "C2-1") (pin "1") (pinfunction "1_1") (pintype "passive"))
      (node (ref "C2-11") (pin "2") (pinfunction "2_2") (pintype "passive"))
      (node (ref "C2-12") (pin "2") (pinfunction "2_2") (pintype "passive"))
      (node (ref "C2-2") (pin "1") (pinfunction "1_1") (pintype "passive"))
      (node (ref "C3-1") (pin "1") (pinfunction "1_1") (pintype "passive"))
      (node (ref "C3-11") (pin "2") (pinfunction "2_2") (pintype "passive"))
      (node (ref "C3-12") (pin "2") (pinfunction "2_2") (pintype "passive"))
      (node (ref "C3-2") (pin "1") (pinfunction "1_1") (pintype "passive"))
      (node (ref "C4") (pin "2") (pinfunction "2_2") (pintype "passive"))
      (node (ref "C4-1") (pin "1") (pinfunction "1_1") (pintype "passive"))
      (node (ref "C4-11") (pin "2") (pinfunction "2_2") (pintype "passive"))
      (node (ref "C4-12") (pin "2") (pinfunction "2_2") (pintype "passive"))
      (node (ref "C4-2") (pin "1") (pinfunction "1_1") (pintype "passive"))
      (node (ref "C5") (pin "2") (pinfunction "2_2") (pintype "passive"))
      (node (ref "C6") (pin "2") (pinfunction "2_2") (pintype "passive"))
      (node (ref "C7") (pin "2") (pinfunction "2_2") (pintype "passive"))
      (node (ref "C8") (pin "2") (pinfunction "2_2") (pintype "passive"))
      (node (ref "P2") (pin "2") (pinfunction "2_2") (pintype "passive"))
      (node (ref "U1") (pin "4") (pinfunction "GND_4") (pintype "passive"))
      (node (ref "U2") (pin "4") (pinfunction "GND_4") (pintype "passive"))
    )
    (net (code "33") (name "Net-(AD1-AIN1)") (class "Default")
      (node (ref "AD1") (pin "11") (pinfunction "AIN1_11") (pintype "passive"))
      (node (ref "C1-3") (pin "2") (pinfunction "2_2") (pintype "passive"))
      (node (ref "C1-4") (pin "1") (pinfunction "1_1") (pintype "passive"))
      (node (ref "R1-1") (pin "2") (pinfunction "2_2") (pintype "passive"))
    )
    (net (code "34") (name "Net-(AD1-AIN2)") (class "Default")
      (node (ref "AD1") (pin "12") (pinfunction "AIN2_12") (pintype "passive"))
      (node (ref "C1-3") (pin "1") (pinfunction "1_1") (pintype "passive"))
      (node (ref "C1-5") (pin "1") (pinfunction "1_1") (pintype "passive"))
      (node (ref "R1-2") (pin "2") (pinfunction "2_2") (pintype "passive"))
    )
    (net (code "35") (name "Net-(AD1-AINCOM)") (class "Default")
      (node (ref "AD1") (pin "10") (pinfunction "AINCOM_10") (pintype "passive"))
      (node (ref "R1-3") (pin "2") (pinfunction "2_2") (pintype "passive"))
    )
    (net (code "36") (name "Net-(AD1-MCLK1)") (class "Default")
      (node (ref "AD1") (pin "1") (pinfunction "MCLK1_1") (pintype "passive"))
      (node (ref "C1-1") (pin "2") (pinfunction "2_2") (pintype "passive"))
      (node (ref "XTAL1") (pin "1") (pinfunction "OSC1_1") (pintype "passive"))
    )
    (net (code "37") (name "Net-(AD1-MCLK2)") (class "Default")
      (node (ref "AD1") (pin "2") (pinfunction "MCLK2_2") (pintype "passive"))
      (node (ref "C1-2") (pin "2") (pinfunction "2_2") (pintype "passive"))
      (node (ref "XTAL1") (pin "2") (pinfunction "OSC2_2") (pintype "passive"))
    )
    (net (code "38") (name "Net-(AD2-AIN1)") (class "Default")
      (node (ref "AD2") (pin "11") (pinfunction "AIN1_11") (pintype "passive"))
      (node (ref "C2-3") (pin "2") (pinfunction "2_2") (pintype "passive"))
      (node (ref "C2-4") (pin "1") (pinfunction "1_1") (pintype "passive"))
      (node (ref "R2-1") (pin "2") (pinfunction "2_2") (pintype "passive"))
    )
    (net (code "39") (name "Net-(AD2-AIN2)") (class "Default")
      (node (ref "AD2") (pin "12") (pinfunction "AIN2_12") (pintype "passive"))
      (node (ref "C2-3") (pin "1") (pinfunction "1_1") (pintype "passive"))
      (node (ref "C2-5") (pin "1") (pinfunction "1_1") (pintype "passive"))
      (node (ref "R2-2") (pin "2") (pinfunction "2_2") (pintype "passive"))
    )
    (net (code "40") (name "Net-(AD2-AINCOM)") (class "Default")
      (node (ref "AD2") (pin "10") (pinfunction "AINCOM_10") (pintype "passive"))
      (node (ref "R2-3") (pin "2") (pinfunction "2_2") (pintype "passive"))
    )
    (net (code "41") (name "Net-(AD2-MCLK1)") (class "Default")
      (node (ref "AD2") (pin "1") (pinfunction "MCLK1_1") (pintype "passive"))
      (node (ref "C2-1") (pin "2") (pinfunction "2_2") (pintype "passive"))
      (node (ref "XTAL2") (pin "1") (pinfunction "OSC1_1") (pintype "passive"))
    )
    (net (code "42") (name "Net-(AD2-MCLK2)") (class "Default")
      (node (ref "AD2") (pin "2") (pinfunction "MCLK2_2") (pintype "passive"))
      (node (ref "C2-2") (pin "2") (pinfunction "2_2") (pintype "passive"))
      (node (ref "XTAL2") (pin "2") (pinfunction "OSC2_2") (pintype "passive"))
    )
    (net (code "43") (name "Net-(AD3-AIN1)") (class "Default")
      (node (ref "AD3") (pin "11") (pinfunction "AIN1_11") (pintype "passive"))
      (node (ref "C3-3") (pin "2") (pinfunction "2_2") (pintype "passive"))
      (node (ref "C3-4") (pin "1") (pinfunction "1_1") (pintype "passive"))
      (node (ref "R3-1") (pin "2") (pinfunction "2_2") (pintype "passive"))
    )
    (net (code "44") (name "Net-(AD3-AIN2)") (class "Default")
      (node (ref "AD3") (pin "12") (pinfunction "AIN2_12") (pintype "passive"))
      (node (ref "C3-3") (pin "1") (pinfunction "1_1") (pintype "passive"))
      (node (ref "C3-5") (pin "1") (pinfunction "1_1") (pintype "passive"))
      (node (ref "R3-2") (pin "2") (pinfunction "2_2") (pintype "passive"))
    )
    (net (code "45") (name "Net-(AD3-AINCOM)") (class "Default")
      (node (ref "AD3") (pin "10") (pinfunction "AINCOM_10") (pintype "passive"))
      (node (ref "R3-3") (pin "2") (pinfunction "2_2") (pintype "passive"))
    )
    (net (code "46") (name "Net-(AD3-MCLK1)") (class "Default")
      (node (ref "AD3") (pin "1") (pinfunction "MCLK1_1") (pintype "passive"))
      (node (ref "C3-1") (pin "2") (pinfunction "2_2") (pintype "passive"))
      (node (ref "XTAL3") (pin "1") (pinfunction "OSC1_1") (pintype "passive"))
    )
    (net (code "47") (name "Net-(AD3-MCLK2)") (class "Default")
      (node (ref "AD3") (pin "2") (pinfunction "MCLK2_2") (pintype "passive"))
      (node (ref "C3-2") (pin "2") (pinfunction "2_2") (pintype "passive"))
      (node (ref "XTAL3") (pin "2") (pinfunction "OSC2_2") (pintype "passive"))
    )
    (net (code "48") (name "Net-(AD4-AIN1)") (class "Default")
      (node (ref "AD4") (pin "11") (pinfunction "AIN1_11") (pintype "passive"))
      (node (ref "C4-3") (pin "2") (pinfunction "2_2") (pintype "passive"))
      (node (ref "C4-4") (pin "1") (pinfunction "1_1") (pintype "passive"))
      (node (ref "R4-1") (pin "2") (pinfunction "2_2") (pintype "passive"))
    )
    (net (code "49") (name "Net-(AD4-AIN2)") (class "Default")
      (node (ref "AD4") (pin "12") (pinfunction "AIN2_12") (pintype "passive"))
      (node (ref "C4-3") (pin "1") (pinfunction "1_1") (pintype "passive"))
      (node (ref "C4-5") (pin "1") (pinfunction "1_1") (pintype "passive"))
      (node (ref "R4-2") (pin "2") (pinfunction "2_2") (pintype "passive"))
    )
    (net (code "50") (name "Net-(AD4-AINCOM)") (class "Default")
      (node (ref "AD4") (pin "10") (pinfunction "AINCOM_10") (pintype "passive"))
      (node (ref "R4-3") (pin "2") (pinfunction "2_2") (pintype "passive"))
    )
    (net (code "51") (name "Net-(AD4-MCLK1)") (class "Default")
      (node (ref "AD4") (pin "1") (pinfunction "MCLK1_1") (pintype "passive"))
      (node (ref "C4-1") (pin "2") (pinfunction "2_2") (pintype "passive"))
      (node (ref "XTAL4") (pin "1") (pinfunction "OSC1_1") (pintype "passive"))
    )
    (net (code "52") (name "Net-(AD4-MCLK2)") (class "Default")
      (node (ref "AD4") (pin "2") (pinfunction "MCLK2_2") (pintype "passive"))
      (node (ref "C4-2") (pin "2") (pinfunction "2_2") (pintype "passive"))
      (node (ref "XTAL4") (pin "2") (pinfunction "OSC2_2") (pintype "passive"))
    )
    (net (code "53") (name "Net-(D1-K)") (class "Default")
      (node (ref "C1") (pin "1") (pinfunction "1_1") (pintype "passive"))
      (node (ref "C2") (pin "1") (pinfunction "1_1") (pintype "passive"))
      (node (ref "D1") (pin "2") (pinfunction "K_2") (pintype "passive"))
      (node (ref "R3") (pin "1") (pinfunction "1_1") (pintype "passive"))
      (node (ref "U1") (pin "5") (pinfunction "~{SD}_5") (pintype "passive"))
      (node (ref "U1") (pin "7") (pinfunction "IN_7") (pintype "passive"))
      (node (ref "U1") (pin "8") (pinfunction "IN_8") (pintype "passive"))
    )
    (net (code "54") (name "Net-(FB-Pad2)") (class "Default")
      (node (ref "FB") (pin "2") (pinfunction "2_2") (pintype "passive"))
      (node (ref "R1") (pin "1") (pinfunction "1_1") (pintype "passive"))
    )
    (net (code "55") (name "Net-(U1-NR)") (class "Default")
      (node (ref "C3") (pin "2") (pinfunction "2_2") (pintype "passive"))
      (node (ref "U1") (pin "3") (pinfunction "NR_3") (pintype "passive"))
    )
    (net (code "56") (name "Net-(U2-VIN)") (class "Default")
      (node (ref "C5") (pin "1") (pinfunction "1_1") (pintype "passive"))
      (node (ref "C6") (pin "1") (pinfunction "1_1") (pintype "passive"))
      (node (ref "R2") (pin "1") (pinfunction "1_1") (pintype "passive"))
      (node (ref "R3") (pin "2") (pinfunction "2_2") (pintype "passive"))
      (node (ref "U2") (pin "2") (pinfunction "VIN_2") (pintype "passive"))
    )
    (net (code "57") (name "Net-(U2-VOUT)") (class "Default")
      (node (ref "C7") (pin "1") (pinfunction "1_1") (pintype "passive"))
      (node (ref "C8") (pin "1") (pinfunction "1_1") (pintype "passive"))
      (node (ref "FB") (pin "1") (pinfunction "1_1") (pintype "passive"))
      (node (ref "U2") (pin "6") (pinfunction "VOUT_6") (pintype "passive"))
    )
    (net (code "58") (name "VCC") (class "Default")
      (node (ref "D1") (pin "1") (pinfunction "A_1") (pintype "passive"))
      (node (ref "P2") (pin "1") (pinfunction "1_1") (pintype "passive"))
    )
    (net (code "59") (name "unconnected-(AD1-AIN3-Pad13)") (class "Default")
      (node (ref "AD1") (pin "13") (pinfunction "AIN3_13") (pintype "passive+no_connect"))
    )
    (net (code "60") (name "unconnected-(AD1-AIN4-Pad14)") (class "Default")
      (node (ref "AD1") (pin "14") (pinfunction "AIN4_14") (pintype "passive+no_connect"))
    )
    (net (code "61") (name "unconnected-(AD1-NC-Pad9)") (class "Default")
      (node (ref "AD1") (pin "9") (pinfunction "NC_9") (pintype "passive+no_connect"))
    )
    (net (code "62") (name "unconnected-(AD1-P0{slash}REFIN2(-)-Pad8)") (class "Default")
      (node (ref "AD1") (pin "8") (pinfunction "P0/REFIN2(-)_8") (pintype "passive+no_connect"))
    )
    (net (code "63") (name "unconnected-(AD1-P1{slash}REFIN2(+)-Pad7)") (class "Default")
      (node (ref "AD1") (pin "7") (pinfunction "P1/REFIN2(+)_7") (pintype "passive+no_connect"))
    )
    (net (code "64") (name "unconnected-(AD1-P2-Pad6)") (class "Default")
      (node (ref "AD1") (pin "6") (pinfunction "P2_6") (pintype "passive+no_connect"))
    )
    (net (code "65") (name "unconnected-(AD1-P3-Pad5)") (class "Default")
      (node (ref "AD1") (pin "5") (pinfunction "P3_5") (pintype "passive+no_connect"))
    )
    (net (code "66") (name "unconnected-(AD2-AIN3-Pad13)") (class "Default")
      (node (ref "AD2") (pin "13") (pinfunction "AIN3_13") (pintype "passive+no_connect"))
    )
    (net (code "67") (name "unconnected-(AD2-AIN4-Pad14)") (class "Default")
      (node (ref "AD2") (pin "14") (pinfunction "AIN4_14") (pintype "passive+no_connect"))
    )
    (net (code "68") (name "unconnected-(AD2-NC-Pad9)") (class "Default")
      (node (ref "AD2") (pin "9") (pinfunction "NC_9") (pintype "passive+no_connect"))
    )
    (net (code "69") (name "unconnected-(AD2-P0{slash}REFIN2(-)-Pad8)") (class "Default")
      (node (ref "AD2") (pin "8") (pinfunction "P0/REFIN2(-)_8") (pintype "passive+no_connect"))
    )
    (net (code "70") (name "unconnected-(AD2-P1{slash}REFIN2(+)-Pad7)") (class "Default")
      (node (ref "AD2") (pin "7") (pinfunction "P1/REFIN2(+)_7") (pintype "passive+no_connect"))
    )
    (net (code "71") (name "unconnected-(AD2-P2-Pad6)") (class "Default")
      (node (ref "AD2") (pin "6") (pinfunction "P2_6") (pintype "passive+no_connect"))
    )
    (net (code "72") (name "unconnected-(AD2-P3-Pad5)") (class "Default")
      (node (ref "AD2") (pin "5") (pinfunction "P3_5") (pintype "passive+no_connect"))
    )
    (net (code "73") (name "unconnected-(AD3-AIN3-Pad13)") (class "Default")
      (node (ref "AD3") (pin "13") (pinfunction "AIN3_13") (pintype "passive+no_connect"))
    )
    (net (code "74") (name "unconnected-(AD3-AIN4-Pad14)") (class "Default")
      (node (ref "AD3") (pin "14") (pinfunction "AIN4_14") (pintype "passive+no_connect"))
    )
    (net (code "75") (name "unconnected-(AD3-NC-Pad9)") (class "Default")
      (node (ref "AD3") (pin "9") (pinfunction "NC_9") (pintype "passive+no_connect"))
    )
    (net (code "76") (name "unconnected-(AD3-P0{slash}REFIN2(-)-Pad8)") (class "Default")
      (node (ref "AD3") (pin "8") (pinfunction "P0/REFIN2(-)_8") (pintype "passive+no_connect"))
    )
    (net (code "77") (name "unconnected-(AD3-P1{slash}REFIN2(+)-Pad7)") (class "Default")
      (node (ref "AD3") (pin "7") (pinfunction "P1/REFIN2(+)_7") (pintype "passive+no_connect"))
    )
    (net (code "78") (name "unconnected-(AD3-P2-Pad6)") (class "Default")
      (node (ref "AD3") (pin "6") (pinfunction "P2_6") (pintype "passive+no_connect"))
    )
    (net (code "79") (name "unconnected-(AD3-P3-Pad5)") (class "Default")
      (node (ref "AD3") (pin "5") (pinfunction "P3_5") (pintype "passive+no_connect"))
    )
    (net (code "80") (name "unconnected-(AD4-AIN3-Pad13)") (class "Default")
      (node (ref "AD4") (pin "13") (pinfunction "AIN3_13") (pintype "passive+no_connect"))
    )
    (net (code "81") (name "unconnected-(AD4-AIN4-Pad14)") (class "Default")
      (node (ref "AD4") (pin "14") (pinfunction "AIN4_14") (pintype "passive+no_connect"))
    )
    (net (code "82") (name "unconnected-(AD4-NC-Pad9)") (class "Default")
      (node (ref "AD4") (pin "9") (pinfunction "NC_9") (pintype "passive+no_connect"))
    )
    (net (code "83") (name "unconnected-(AD4-P0{slash}REFIN2(-)-Pad8)") (class "Default")
      (node (ref "AD4") (pin "8") (pinfunction "P0/REFIN2(-)_8") (pintype "passive+no_connect"))
    )
    (net (code "84") (name "unconnected-(AD4-P1{slash}REFIN2(+)-Pad7)") (class "Default")
      (node (ref "AD4") (pin "7") (pinfunction "P1/REFIN2(+)_7") (pintype "passive+no_connect"))
    )
    (net (code "85") (name "unconnected-(AD4-P2-Pad6)") (class "Default")
      (node (ref "AD4") (pin "6") (pinfunction "P2_6") (pintype "passive+no_connect"))
    )
    (net (code "86") (name "unconnected-(AD4-P3-Pad5)") (class "Default")
      (node (ref "AD4") (pin "5") (pinfunction "P3_5") (pintype "passive+no_connect"))
    )
    (net (code "87") (name "unconnected-(U1-~{ERR}-Pad6)") (class "Default")
      (node (ref "U1") (pin "6") (pinfunction "~{ERR}_6") (pintype "passive+no_connect"))
    )
    (net (code "88") (name "unconnected-(U2-DNC-Pad1)") (class "Default")
      (node (ref "U2") (pin "1") (pinfunction "DNC_1") (pintype "passive+no_connect"))
    )
    (net (code "89") (name "unconnected-(U2-DNC-Pad5)") (class "Default")
      (node (ref "U2") (pin "5") (pinfunction "DNC_5") (pintype "passive+no_connect"))
    )
    (net (code "90") (name "unconnected-(U2-DNC-Pad7)") (class "Default")
      (node (ref "U2") (pin "7") (pinfunction "DNC_7") (pintype "passive+no_connect"))
    )
    (net (code "91") (name "unconnected-(U2-DNC-Pad8)") (class "Default")
      (node (ref "U2") (pin "8") (pinfunction "DNC_8") (pintype "passive+no_connect"))
    )
    (net (code "92") (name "unconnected-(U2-~{SHDN}-Pad3)") (class "Default")
      (node (ref "U2") (pin "3") (pinfunction "~{SHDN}_3") (pintype "passive+no_connect"))
    )
  )
)
